# sound.net
KiCad netlist of a schematic drawn in Altium Designer
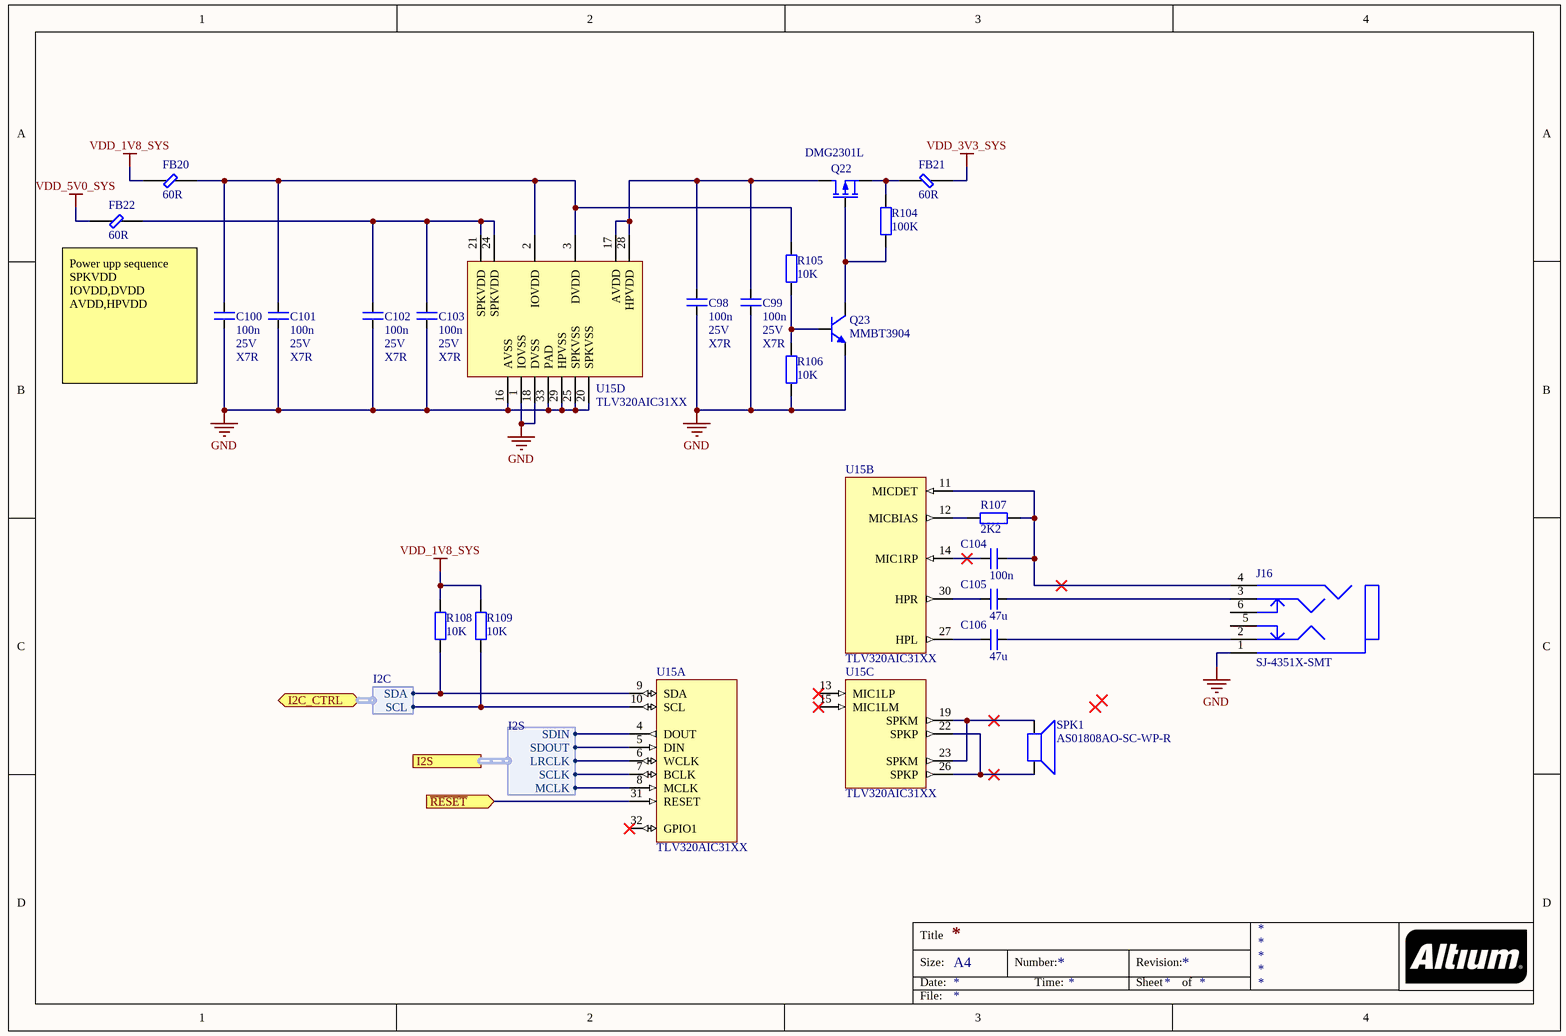
[diagram p0: sound.SchDoc]

(export (version "E")
  (design (tool "Eeschema 10.0.6"))
  (components
    (comp (ref "C98")
      (value "100n")
      (footprint "C1005[0402]")
      (description "Capacitor")
      (fields (field (name "VOLTAGE") "25V") (field (name "TYPE") "X7R") (field (name "Comment") "cap"))
      (libsource (lib "gpa_passives") (part "cap"))
    )
    (comp (ref "C99")
      (value "100n")
      (footprint "C1005[0402]")
      (description "Capacitor")
      (fields (field (name "VOLTAGE") "25V") (field (name "TYPE") "X7R") (field (name "Comment") "cap"))
      (libsource (lib "gpa_passives") (part "cap"))
    )
    (comp (ref "C100")
      (value "100n")
      (footprint "C1005[0402]")
      (description "Capacitor")
      (fields (field (name "VOLTAGE") "25V") (field (name "TYPE") "X7R") (field (name "Comment") "cap"))
      (libsource (lib "gpa_passives") (part "cap"))
    )
    (comp (ref "C101")
      (value "100n")
      (footprint "C1005[0402]")
      (description "Capacitor")
      (fields (field (name "VOLTAGE") "25V") (field (name "TYPE") "X7R") (field (name "Comment") "cap"))
      (libsource (lib "gpa_passives") (part "cap"))
    )
    (comp (ref "C102")
      (value "100n")
      (footprint "C1005[0402]")
      (description "Capacitor")
      (fields (field (name "VOLTAGE") "25V") (field (name "TYPE") "X7R") (field (name "Comment") "cap"))
      (libsource (lib "gpa_passives") (part "cap"))
    )
    (comp (ref "C103")
      (value "100n")
      (footprint "C1005[0402]")
      (description "Capacitor")
      (fields (field (name "VOLTAGE") "25V") (field (name "TYPE") "X7R") (field (name "Comment") "cap"))
      (libsource (lib "gpa_passives") (part "cap"))
    )
    (comp (ref "C104")
      (value "100n")
      (footprint "C3216[1206]")
      (description "Capacitor")
      (fields (field (name "VOLTAGE") "25V") (field (name "Comment") "cap"))
      (libsource (lib "gpa_passives") (part "cap"))
    )
    (comp (ref "C105")
      (value "47u")
      (footprint "C3216[1206]")
      (description "Capacitor")
      (fields (field (name "VOLTAGE") "25V") (field (name "Comment") "cap"))
      (libsource (lib "gpa_passives") (part "cap"))
    )
    (comp (ref "C106")
      (value "47u")
      (footprint "C3216[1206]")
      (description "Capacitor")
      (fields (field (name "VOLTAGE") "25V") (field (name "Comment") "cap"))
      (libsource (lib "gpa_passives") (part "cap"))
    )
    (comp (ref "FB20")
      (value "60R")
      (footprint "FBC1608X07N")
      (description "Ferrite bead")
      (libsource (lib "gpa_passives") (part "ferrite_bead"))
    )
    (comp (ref "FB21")
      (value "60R")
      (footprint "FBC1608X07N")
      (description "Ferrite bead")
      (libsource (lib "gpa_passives") (part "ferrite_bead"))
    )
    (comp (ref "FB22")
      (value "60R")
      (footprint "FBC1608X07N")
      (description "Ferrite bead")
      (libsource (lib "gpa_passives") (part "ferrite_bead"))
    )
    (comp (ref "J16")
      (value "SJ-4351X-SMT")
      (footprint "CUI_SJ-4351X-SMT")
      (libsource (lib "gpa_connectors") (part "3.5mm_headset_4pole"))
    )
    (comp (ref "Q22")
      (value "DMG2301L")
      (footprint "NCH_SOT95P237X110-3N")
      (libsource (lib "gpa_actives") (part "pch_mosfet"))
    )
    (comp (ref "Q23")
      (value "MMBT3904")
      (footprint "NPN_SOT95P230X110-3N")
      (description "NPN Bipolar Transistor")
      (fields (field (name "PUBLISHER") "Altium Limited"))
      (libsource (lib "gpa_actives") (part "npn_bipolar"))
    )
    (comp (ref "R104")
      (value "100K")
      (footprint "R1005[0402]")
      (description "Resistor")
      (fields (field (name "Comment") "res"))
      (libsource (lib "") (part "res_1"))
    )
    (comp (ref "R105")
      (value "10K")
      (footprint "R1005[0402]")
      (description "Resistor")
      (fields (field (name "Comment") "res"))
      (libsource (lib "gpa_passives") (part "res"))
    )
    (comp (ref "R106")
      (value "10K")
      (footprint "R1005[0402]")
      (description "Resistor")
      (fields (field (name "Comment") "res"))
      (libsource (lib "") (part "res_2"))
    )
    (comp (ref "R107")
      (value "2K2")
      (footprint "R1005[0402]")
      (description "Resistor")
      (fields (field (name "Comment") "res"))
      (libsource (lib "") (part "res_3"))
    )
    (comp (ref "R108")
      (value "10K")
      (footprint "R1005[0402]")
      (description "Resistor")
      (fields (field (name "Comment") "res"))
      (libsource (lib "") (part "res_1"))
    )
    (comp (ref "R109")
      (value "10K")
      (footprint "R1005[0402]")
      (description "Resistor")
      (fields (field (name "Comment") "res"))
      (libsource (lib "") (part "res_1"))
    )
    (comp (ref "SPK1")
      (value "AS01808AO-SC-WP-R")
      (footprint "pui_audio_speaker")
      (libsource (lib "gpa_actives") (part "speaker"))
    )
    (comp (ref "U15")
      (value "TLV320AIC31XX")
      (footprint "TI_QFN50P500X500X100_HS-33M")
      (libsource (lib "gpa_ti") (part "tlv320aic3100"))
    )
  )
  (nets
    (net (code "3") (name "/LRCLK") (class "Default")
      (node (ref "U15") (pin "6") (pinfunction "WCLK_6") (pintype "bidirectional"))
    )
    (net (code "4") (name "/MCLK") (class "Default")
      (node (ref "U15") (pin "8") (pinfunction "MCLK_8") (pintype "input"))
    )
    (net (code "5") (name "/RESET") (class "Default")
      (node (ref "U15") (pin "31") (pinfunction "RESET_31") (pintype "input"))
    )
    (net (code "6") (name "/SCL") (class "Default")
      (node (ref "R109") (pin "1") (pinfunction "1_1") (pintype "passive"))
      (node (ref "U15") (pin "10") (pinfunction "SCL_10") (pintype "bidirectional"))
    )
    (net (code "7") (name "/SCLK") (class "Default")
      (node (ref "U15") (pin "7") (pinfunction "BCLK_7") (pintype "bidirectional"))
    )
    (net (code "8") (name "/SDA") (class "Default")
      (node (ref "R108") (pin "1") (pinfunction "1_1") (pintype "passive"))
      (node (ref "U15") (pin "9") (pinfunction "SDA_9") (pintype "bidirectional"))
    )
    (net (code "9") (name "/SDIN") (class "Default")
      (node (ref "U15") (pin "4") (pinfunction "DOUT_4") (pintype "output"))
    )
    (net (code "10") (name "/SDOUT") (class "Default")
      (node (ref "U15") (pin "5") (pinfunction "DIN_5") (pintype "input"))
    )
    (net (code "13") (name "GND") (class "Default")
      (node (ref "C100") (pin "1") (pinfunction "1_1") (pintype "passive"))
      (node (ref "C101") (pin "1") (pinfunction "1_1") (pintype "passive"))
      (node (ref "C102") (pin "1") (pinfunction "1_1") (pintype "passive"))
      (node (ref "C103") (pin "1") (pinfunction "1_1") (pintype "passive"))
      (node (ref "C98") (pin "1") (pinfunction "1_1") (pintype "passive"))
      (node (ref "C99") (pin "1") (pinfunction "1_1") (pintype "passive"))
      (node (ref "J16") (pin "1") (pinfunction "1_1") (pintype "passive"))
      (node (ref "Q23") (pin "E") (pinfunction "E_E") (pintype "passive"))
      (node (ref "R106") (pin "1") (pinfunction "1_1") (pintype "passive"))
      (node (ref "U15") (pin "1") (pinfunction "IOVSS_1") (pintype "power_in"))
      (node (ref "U15") (pin "16") (pinfunction "AVSS_16") (pintype "power_in"))
      (node (ref "U15") (pin "18") (pinfunction "DVSS_18") (pintype "power_in"))
      (node (ref "U15") (pin "20") (pinfunction "SPKVSS_20") (pintype "power_in"))
      (node (ref "U15") (pin "25") (pinfunction "SPKVSS_25") (pintype "power_in"))
      (node (ref "U15") (pin "29") (pinfunction "HPVSS_29") (pintype "power_in"))
      (node (ref "U15") (pin "33") (pinfunction "PAD_33") (pintype "power_in"))
    )
    (net (code "14") (name "Net-(C102-Pad2)") (class "Default")
      (node (ref "C102") (pin "2") (pinfunction "2_2") (pintype "passive"))
      (node (ref "C103") (pin "2") (pinfunction "2_2") (pintype "passive"))
      (node (ref "FB22") (pin "2") (pinfunction "2_2") (pintype "passive"))
      (node (ref "U15") (pin "21") (pinfunction "SPKVDD_21") (pintype "power_in"))
      (node (ref "U15") (pin "24") (pinfunction "SPKVDD_24") (pintype "power_in"))
    )
    (net (code "15") (name "Net-(C105-Pad2)") (class "Default")
      (node (ref "C105") (pin "2") (pinfunction "2_2") (pintype "passive"))
      (node (ref "J16") (pin "3") (pinfunction "3_3") (pintype "passive"))
    )
    (net (code "16") (name "Net-(C106-Pad2)") (class "Default")
      (node (ref "C106") (pin "2") (pinfunction "2_2") (pintype "passive"))
      (node (ref "J16") (pin "2") (pinfunction "2_2") (pintype "passive"))
    )
    (net (code "17") (name "Net-(FB21-Pad2)") (class "Default")
      (node (ref "FB21") (pin "2") (pinfunction "2_2") (pintype "passive"))
      (node (ref "Q22") (pin "S") (pinfunction "S_S") (pintype "passive"))
      (node (ref "R104") (pin "2") (pinfunction "2_2") (pintype "passive"))
    )
    (net (code "18") (name "Net-(Q22-PadG)") (class "Default")
      (node (ref "Q22") (pin "G") (pinfunction "G_G") (pintype "passive"))
      (node (ref "Q23") (pin "C") (pinfunction "C_C") (pintype "passive"))
      (node (ref "R104") (pin "1") (pinfunction "1_1") (pintype "passive"))
    )
    (net (code "19") (name "Net-(Q23-PadB)") (class "Default")
      (node (ref "Q23") (pin "B") (pinfunction "B_B") (pintype "passive"))
      (node (ref "R105") (pin "2") (pinfunction "2_2") (pintype "passive"))
      (node (ref "R106") (pin "2") (pinfunction "2_2") (pintype "passive"))
    )
    (net (code "20") (name "Net-(SPK1-Pad1)") (class "Default")
      (node (ref "SPK1") (pin "1") (pinfunction "1_1") (pintype "passive"))
      (node (ref "U15") (pin "19") (pinfunction "SPKM_19") (pintype "output"))
      (node (ref "U15") (pin "23") (pinfunction "SPKM_23") (pintype "output"))
    )
    (net (code "21") (name "Net-(SPK1-Pad2)") (class "Default")
      (node (ref "SPK1") (pin "2") (pinfunction "2_2") (pintype "passive"))
      (node (ref "U15") (pin "22") (pinfunction "SPKP_22") (pintype "output"))
      (node (ref "U15") (pin "26") (pinfunction "SPKP_26") (pintype "output"))
    )
    (net (code "22") (name "Net-(U15B-HPL)") (class "Default")
      (node (ref "C106") (pin "1") (pinfunction "1_1") (pintype "passive"))
      (node (ref "U15") (pin "27") (pinfunction "HPL_27") (pintype "output"))
    )
    (net (code "23") (name "Net-(U15B-HPR)") (class "Default")
      (node (ref "C105") (pin "1") (pinfunction "1_1") (pintype "passive"))
      (node (ref "U15") (pin "30") (pinfunction "HPR_30") (pintype "output"))
    )
    (net (code "24") (name "Net-(U15B-MIC1RP)") (class "Default")
      (node (ref "C104") (pin "1") (pinfunction "1_1") (pintype "passive"))
      (node (ref "U15") (pin "14") (pinfunction "MIC1RP_14") (pintype "input"))
    )
    (net (code "25") (name "Net-(U15B-MICBIAS)") (class "Default")
      (node (ref "R107") (pin "2") (pinfunction "2_2") (pintype "passive"))
      (node (ref "U15") (pin "12") (pinfunction "MICBIAS_12") (pintype "output"))
    )
    (net (code "26") (name "Net-(U15B-MICDET)") (class "Default")
      (node (ref "C104") (pin "2") (pinfunction "2_2") (pintype "passive"))
      (node (ref "J16") (pin "4") (pinfunction "4_4") (pintype "passive"))
      (node (ref "R107") (pin "1") (pinfunction "1_1") (pintype "passive"))
      (node (ref "U15") (pin "11") (pinfunction "MICDET_11") (pintype "input"))
    )
    (net (code "27") (name "Net-(U15D-AVDD)") (class "Default")
      (node (ref "C98") (pin "2") (pinfunction "2_2") (pintype "passive"))
      (node (ref "C99") (pin "2") (pinfunction "2_2") (pintype "passive"))
      (node (ref "Q22") (pin "D") (pinfunction "D_D") (pintype "passive"))
      (node (ref "U15") (pin "17") (pinfunction "AVDD_17") (pintype "power_in"))
      (node (ref "U15") (pin "28") (pinfunction "HPVDD_28") (pintype "power_in"))
    )
    (net (code "28") (name "Net-(U15D-DVDD)") (class "Default")
      (node (ref "C100") (pin "2") (pinfunction "2_2") (pintype "passive"))
      (node (ref "C101") (pin "2") (pinfunction "2_2") (pintype "passive"))
      (node (ref "FB20") (pin "2") (pinfunction "2_2") (pintype "passive"))
      (node (ref "R105") (pin "1") (pinfunction "1_1") (pintype "passive"))
      (node (ref "U15") (pin "2") (pinfunction "IOVDD_2") (pintype "power_in"))
      (node (ref "U15") (pin "3") (pinfunction "DVDD_3") (pintype "power_in"))
    )
    (net (code "29") (name "VDD_1V8_SYS") (class "Default")
      (node (ref "FB20") (pin "1") (pinfunction "1_1") (pintype "passive"))
      (node (ref "R108") (pin "2") (pinfunction "2_2") (pintype "passive"))
      (node (ref "R109") (pin "2") (pinfunction "2_2") (pintype "passive"))
    )
    (net (code "30") (name "VDD_3V3_SYS") (class "Default")
      (node (ref "FB21") (pin "1") (pinfunction "1_1") (pintype "passive"))
    )
    (net (code "31") (name "VDD_5V0_SYS") (class "Default")
      (node (ref "FB22") (pin "1") (pinfunction "1_1") (pintype "passive"))
    )
    (net (code "32") (name "unconnected-(J16-Pad5)") (class "Default")
      (node (ref "J16") (pin "5") (pinfunction "5_5") (pintype "passive"))
    )
    (net (code "33") (name "unconnected-(J16-Pad6)") (class "Default")
      (node (ref "J16") (pin "6") (pinfunction "6_6") (pintype "passive"))
    )
    (net (code "34") (name "unconnected-(U15A-GPIO1-Pad32)") (class "Default")
      (node (ref "U15") (pin "32") (pinfunction "GPIO1_32") (pintype "bidirectional+no_connect"))
    )
    (net (code "35") (name "unconnected-(U15C-MIC1LM-Pad15)") (class "Default")
      (node (ref "U15") (pin "15") (pinfunction "MIC1LM_15") (pintype "input+no_connect"))
    )
    (net (code "36") (name "unconnected-(U15C-MIC1LP-Pad13)") (class "Default")
      (node (ref "U15") (pin "13") (pinfunction "MIC1LP_13") (pintype "input+no_connect"))
    )
  )
)
